# battery_pack.net
KiCad netlist of a schematic drawn in EAGLE
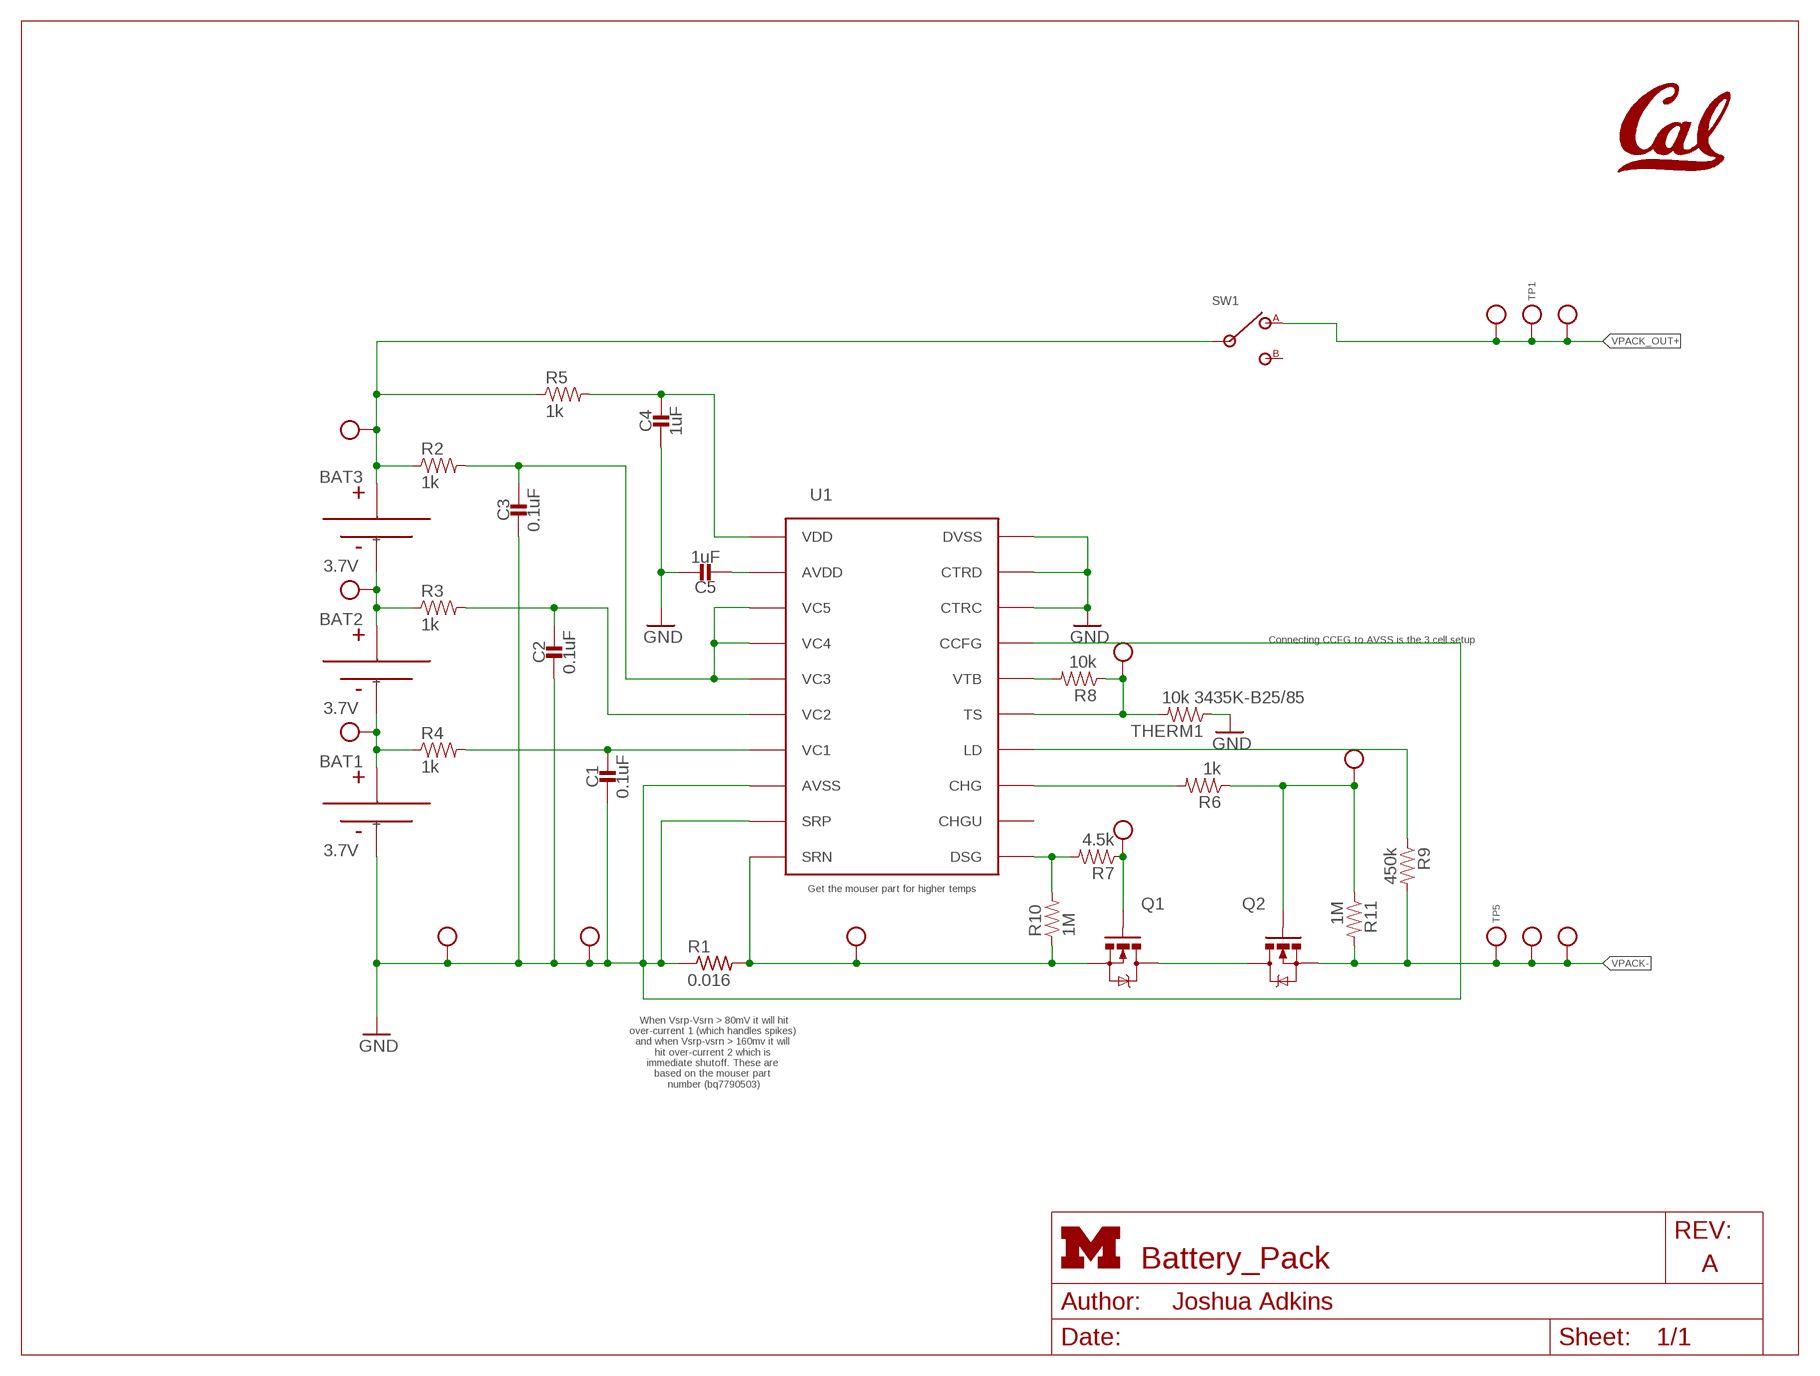
[diagram p0: schematic, sheet 1]

(export (version "E")
  (design (tool "Eeschema 10.0.6"))
  (components
    (comp (ref "BAT1")
      (value "3.7V")
      (footprint "eagle-import:PL-809797-1C")
      (libsource (lib "eagle-import") (part "BAT-CELL"))
    )
    (comp (ref "BAT2")
      (value "3.7V")
      (footprint "eagle-import:PL-809797-1C")
      (libsource (lib "eagle-import") (part "BAT-CELL"))
    )
    (comp (ref "BAT3")
      (value "3.7V")
      (footprint "eagle-import:PL-809797-1C")
      (libsource (lib "eagle-import") (part "BAT-CELL"))
    )
    (comp (ref "C1")
      (value "0.1uF")
      (footprint "eagle-import:0603_CAP")
      (description "CAP CER 0.1UF 25V Y5V 0603")
      (fields (field (name "MANUFACTURER") "Yageo") (field (name "MPN") "CC0603ZRY5V8BB104"))
      (libsource (lib "eagle-import") (part "CAPACITOR0603_CAP"))
    )
    (comp (ref "C2")
      (value "0.1uF")
      (footprint "eagle-import:0603_CAP")
      (description "CAP CER 0.1UF 25V Y5V 0603")
      (fields (field (name "MANUFACTURER") "Yageo") (field (name "MPN") "CC0603ZRY5V8BB104"))
      (libsource (lib "eagle-import") (part "CAPACITOR0603_CAP"))
    )
    (comp (ref "C3")
      (value "0.1uF")
      (footprint "eagle-import:0603_CAP")
      (description "CAP CER 0.1UF 25V Y5V 0603")
      (fields (field (name "MANUFACTURER") "Yageo") (field (name "MPN") "CC0603ZRY5V8BB104"))
      (libsource (lib "eagle-import") (part "CAPACITOR0603_CAP"))
    )
    (comp (ref "C4")
      (value "1uF")
      (footprint "eagle-import:0603_CAP")
      (description "CAP CER 1UF 25V X5R 0603")
      (fields (field (name "MANUFACTURER") "Yageo") (field (name "MPN") "CC0603KRX5R8BB105"))
      (libsource (lib "eagle-import") (part "CAPACITOR0603_CAP"))
    )
    (comp (ref "C5")
      (value "1uF")
      (footprint "eagle-import:0603_CAP")
      (description "CAP CER 1UF 25V X5R 0603")
      (fields (field (name "MANUFACTURER") "Yageo") (field (name "MPN") "CC0603KRX5R8BB105"))
      (libsource (lib "eagle-import") (part "CAPACITOR0603_CAP"))
    )
    (comp (ref "Q1")
      (value "MOSFET-NCHANNELFDD8580")
      (footprint "eagle-import:DPAK")
      (description "MOSFET N-CH 40V 50A DPAK")
      (fields (field (name "MANUFACTURER") "Fairchild Semiconductor") (field (name "MPN") "FDD8447L_F085"))
      (libsource (lib "eagle-import") (part "MOSFET-NCHANNELFDD8580"))
    )
    (comp (ref "Q2")
      (value "MOSFET-NCHANNELFDD8580")
      (footprint "eagle-import:DPAK")
      (description "MOSFET N-CH 40V 50A DPAK")
      (fields (field (name "MANUFACTURER") "Fairchild Semiconductor") (field (name "MPN") "FDD8447L_F085"))
      (libsource (lib "eagle-import") (part "MOSFET-NCHANNELFDD8580"))
    )
    (comp (ref "R1")
      (value "0.016")
      (footprint "eagle-import:R1206")
      (description "RES SMD 16 MOHM 1% 1W 1206")
      (fields (field (name "MANUFACTURER") "Panasonic") (field (name "MPN") "ERJ8CWFR016V"))
      (libsource (lib "eagle-import") (part "R-US_R1206"))
    )
    (comp (ref "R2")
      (value "1k")
      (footprint "eagle-import:0603-RES")
      (description "RES SMD 1K OHM 5% 1/10W 0603")
      (fields (field (name "MANUFACTURER") "Yageo") (field (name "MPN") "RC0603JR-071KL"))
      (libsource (lib "eagle-import") (part "RESISTOR0603_RES"))
    )
    (comp (ref "R3")
      (value "1k")
      (footprint "eagle-import:0603-RES")
      (description "RES SMD 1K OHM 5% 1/10W 0603")
      (fields (field (name "MANUFACTURER") "Yageo") (field (name "MPN") "RC0603JR-071KL"))
      (libsource (lib "eagle-import") (part "RESISTOR0603_RES"))
    )
    (comp (ref "R4")
      (value "1k")
      (footprint "eagle-import:0603-RES")
      (description "RES SMD 1K OHM 5% 1/10W 0603")
      (fields (field (name "MANUFACTURER") "Yageo") (field (name "MPN") "RC0603JR-071KL"))
      (libsource (lib "eagle-import") (part "RESISTOR0603_RES"))
    )
    (comp (ref "R5")
      (value "1k")
      (footprint "eagle-import:0603-RES")
      (description "RES SMD 1K OHM 5% 1/10W 0603")
      (fields (field (name "MANUFACTURER") "Yageo") (field (name "MPN") "RC0603JR-071KL"))
      (libsource (lib "eagle-import") (part "RESISTOR0603_RES"))
    )
    (comp (ref "R6")
      (value "1k")
      (footprint "eagle-import:0603-RES")
      (description "RES SMD 1K OHM 5% 1/10W 0603")
      (fields (field (name "MANUFACTURER") "Yageo") (field (name "MPN") "RC0603JR-071KL"))
      (libsource (lib "eagle-import") (part "RESISTOR0603_RES"))
    )
    (comp (ref "R7")
      (value "4.5k")
      (footprint "eagle-import:0603-RES")
      (description "RES SMD 4.53K OHM 1% 1/10W 0603")
      (fields (field (name "MANUFACTURER") "Yageo") (field (name "MPN") "RC0603FR-074K53L"))
      (libsource (lib "eagle-import") (part "RESISTOR0603_RES"))
    )
    (comp (ref "R8")
      (value "10k")
      (footprint "eagle-import:0603-RES")
      (description "RES SMD 10K OHM 5% 1/10W 0603")
      (fields (field (name "MANUFACTURER") "Yageo") (field (name "MPN") "RC0603JR-0710KL"))
      (libsource (lib "eagle-import") (part "RESISTOR0603_RES"))
    )
    (comp (ref "R9")
      (value "450k")
      (footprint "eagle-import:0603-RES")
      (description "RES SMD 453K OHM 1% 1/10W 0603")
      (fields (field (name "MANUFACTURER") "Yageo") (field (name "MPN") "RC0603FR-07453KL"))
      (libsource (lib "eagle-import") (part "RESISTOR0603_RES"))
    )
    (comp (ref "R10")
      (value "1M")
      (footprint "eagle-import:0603-RES")
      (description "RES SMD 1M OHM 5% 1/10W 0603")
      (fields (field (name "MANUFACTURER") "Yageo") (field (name "MPN") "RC0603JR-071ML"))
      (libsource (lib "eagle-import") (part "RESISTOR0603_RES"))
    )
    (comp (ref "R11")
      (value "1M")
      (footprint "eagle-import:0603-RES")
      (description "RES SMD 1M OHM 5% 1/10W 0603")
      (fields (field (name "MANUFACTURER") "Yageo") (field (name "MPN") "RC0603JR-071ML"))
      (libsource (lib "eagle-import") (part "RESISTOR0603_RES"))
    )
    (comp (ref "SW1")
      (value "500ASSP")
      (footprint "eagle-import:500ASSP")
      (fields (field (name "MANUFACTURER") "EWSITCH") (field (name "MPN") "500ASSP1M6QE"))
      (libsource (lib "eagle-import") (part "500ASSP"))
    )
    (comp (ref "THERM1")
      (value "10k 3435K-B25/85")
      (footprint "eagle-import:0603-RES")
      (description "NTC THERMISTOR 10K OHM 1% 0603")
      (fields (field (name "MANUFACTURER") "TDK") (field (name "MPN") "NTCG163JF103FT1"))
      (libsource (lib "eagle-import") (part "RESISTOR0603_RES"))
    )
    (comp (ref "TP1")
      (value "TEST_POINT_0.060IN")
      (footprint "eagle-import:TESTPOINT_0.060IN")
      (libsource (lib "eagle-import") (part "TEST_POINT_0.060IN"))
    )
    (comp (ref "TP2")
      (value "TEST_POINT_0.112IN")
      (footprint "eagle-import:TESTPOINT_0.112IN")
      (libsource (lib "eagle-import") (part "TEST_POINT_0.112IN"))
    )
    (comp (ref "TP3")
      (value "TEST_POINT_0.040IN")
      (footprint "eagle-import:TESTPOINT_0.040IN")
      (libsource (lib "eagle-import") (part "TEST_POINT_0.040IN"))
    )
    (comp (ref "TP4")
      (value "TEST_POINT_0.040IN")
      (footprint "eagle-import:TESTPOINT_0.040IN")
      (libsource (lib "eagle-import") (part "TEST_POINT_0.040IN"))
    )
    (comp (ref "TP5")
      (value "TEST_POINT_0.060IN")
      (footprint "eagle-import:TESTPOINT_0.060IN")
      (libsource (lib "eagle-import") (part "TEST_POINT_0.060IN"))
    )
    (comp (ref "TP6")
      (value "TEST_POINT_0.112IN")
      (footprint "eagle-import:TESTPOINT_0.112IN")
      (libsource (lib "eagle-import") (part "TEST_POINT_0.112IN"))
    )
    (comp (ref "TP7")
      (value "TEST_POINT_0.112IN")
      (footprint "eagle-import:TESTPOINT_0.112IN")
      (libsource (lib "eagle-import") (part "TEST_POINT_0.112IN"))
    )
    (comp (ref "TP8")
      (value "TEST_POINT_0.112IN")
      (footprint "eagle-import:TESTPOINT_0.112IN")
      (libsource (lib "eagle-import") (part "TEST_POINT_0.112IN"))
    )
    (comp (ref "TP9")
      (value "TEST_POINT_0.040IN")
      (footprint "eagle-import:TESTPOINT_0.040IN")
      (libsource (lib "eagle-import") (part "TEST_POINT_0.040IN"))
    )
    (comp (ref "TP10")
      (value "TEST_POINT_0.040IN")
      (footprint "eagle-import:TESTPOINT_0.040IN")
      (libsource (lib "eagle-import") (part "TEST_POINT_0.040IN"))
    )
    (comp (ref "TP11")
      (value "TEST_POINT_0.040IN")
      (footprint "eagle-import:TESTPOINT_0.040IN")
      (libsource (lib "eagle-import") (part "TEST_POINT_0.040IN"))
    )
    (comp (ref "TP12")
      (value "TEST_POINT_0.040IN")
      (footprint "eagle-import:TESTPOINT_0.040IN")
      (libsource (lib "eagle-import") (part "TEST_POINT_0.040IN"))
    )
    (comp (ref "TP13")
      (value "TEST_POINT_0.040IN")
      (footprint "eagle-import:TESTPOINT_0.040IN")
      (libsource (lib "eagle-import") (part "TEST_POINT_0.040IN"))
    )
    (comp (ref "TP14")
      (value "TEST_POINT_0.112IN")
      (footprint "eagle-import:TESTPOINT_0.112IN")
      (libsource (lib "eagle-import") (part "TEST_POINT_0.112IN"))
    )
    (comp (ref "TP15")
      (value "TEST_POINT_0.112IN")
      (footprint "eagle-import:TESTPOINT_0.112IN")
      (libsource (lib "eagle-import") (part "TEST_POINT_0.112IN"))
    )
    (comp (ref "U$1")
      (value "UCB_CAL500MIL")
      (footprint "eagle-import:UCB_CAL_500MIL")
      (libsource (lib "eagle-import") (part "UCB_CAL500MIL"))
    )
    (comp (ref "U1")
      (value "BQ77904")
      (footprint "eagle-import:TSSOP-20_6MM")
      (fields (field (name "MANUFACTURER") "TI") (field (name "MPN") "BQ7790503PW"))
      (libsource (lib "eagle-import") (part "BQ77904"))
    )
  )
  (nets
    (net (code "1") (name "GND") (class "Default")
      (node (ref "BAT1") (pin "-") (pinfunction "-_-") (pintype "bidirectional"))
      (node (ref "C1") (pin "2") (pinfunction "2_2") (pintype "bidirectional"))
      (node (ref "C2") (pin "2") (pinfunction "2_2") (pintype "bidirectional"))
      (node (ref "C3") (pin "2") (pinfunction "2_2") (pintype "bidirectional"))
      (node (ref "C4") (pin "2") (pinfunction "2_2") (pintype "bidirectional"))
      (node (ref "C5") (pin "1") (pinfunction "1_1") (pintype "bidirectional"))
      (node (ref "R1") (pin "1") (pinfunction "1_1") (pintype "passive"))
      (node (ref "THERM1") (pin "1") (pinfunction "1_1") (pintype "passive"))
      (node (ref "TP7") (pin "1") (pinfunction "TESTPOINT_1") (pintype "bidirectional"))
      (node (ref "TP9") (pin "TESTPOINT") (pinfunction "TESTPOINT_TESTPOINT") (pintype "bidirectional"))
      (node (ref "U1") (pin "17") (pinfunction "CCFG_17") (pintype "bidirectional"))
      (node (ref "U1") (pin "18") (pinfunction "CTRC_18") (pintype "bidirectional"))
      (node (ref "U1") (pin "19") (pinfunction "CTRD_19") (pintype "bidirectional"))
      (node (ref "U1") (pin "20") (pinfunction "DVSS_20") (pintype "bidirectional"))
      (node (ref "U1") (pin "8") (pinfunction "AVSS_8") (pintype "bidirectional"))
      (node (ref "U1") (pin "9") (pinfunction "SRP_9") (pintype "bidirectional"))
    )
    (net (code "2") (name "Net-(Q1-D)") (class "Default")
      (node (ref "Q1") (pin "4") (pinfunction "D_4") (pintype "passive"))
      (node (ref "Q2") (pin "4") (pinfunction "D_4") (pintype "passive"))
    )
    (net (code "3") (name "Net-(Q1-G)") (class "Default")
      (node (ref "Q1") (pin "1") (pinfunction "G_1") (pintype "passive"))
      (node (ref "R7") (pin "1") (pinfunction "1_1") (pintype "passive"))
      (node (ref "TP11") (pin "TESTPOINT") (pinfunction "TESTPOINT_TESTPOINT") (pintype "bidirectional"))
    )
    (net (code "4") (name "Net-(Q1-S)") (class "Default")
      (node (ref "Q1") (pin "3") (pinfunction "S_3") (pintype "passive"))
      (node (ref "R1") (pin "2") (pinfunction "2_2") (pintype "passive"))
      (node (ref "R10") (pin "1") (pinfunction "1_1") (pintype "passive"))
      (node (ref "TP10") (pin "TESTPOINT") (pinfunction "TESTPOINT_TESTPOINT") (pintype "bidirectional"))
      (node (ref "U1") (pin "10") (pinfunction "SRN_10") (pintype "bidirectional"))
    )
    (net (code "5") (name "Net-(Q2-G)") (class "Default")
      (node (ref "Q2") (pin "1") (pinfunction "G_1") (pintype "passive"))
      (node (ref "R11") (pin "1") (pinfunction "1_1") (pintype "passive"))
      (node (ref "R6") (pin "1") (pinfunction "1_1") (pintype "passive"))
      (node (ref "TP12") (pin "TESTPOINT") (pinfunction "TESTPOINT_TESTPOINT") (pintype "bidirectional"))
    )
    (net (code "6") (name "Net-(TP8-TESTPOINT)") (class "Default")
      (node (ref "BAT3") (pin "+") (pinfunction "+_+") (pintype "bidirectional"))
      (node (ref "R2") (pin "1") (pinfunction "1_1") (pintype "passive"))
      (node (ref "R5") (pin "1") (pinfunction "1_1") (pintype "passive"))
      (node (ref "SW1") (pin "2") (pinfunction "2_2") (pintype "bidirectional"))
      (node (ref "TP8") (pin "1") (pinfunction "TESTPOINT_1") (pintype "bidirectional"))
    )
    (net (code "7") (name "Net-(TP14-TESTPOINT)") (class "Default")
      (node (ref "BAT2") (pin "+") (pinfunction "+_+") (pintype "bidirectional"))
      (node (ref "BAT3") (pin "-") (pinfunction "-_-") (pintype "bidirectional"))
      (node (ref "R3") (pin "1") (pinfunction "1_1") (pintype "passive"))
      (node (ref "TP14") (pin "1") (pinfunction "TESTPOINT_1") (pintype "bidirectional"))
    )
    (net (code "8") (name "Net-(TP15-TESTPOINT)") (class "Default")
      (node (ref "BAT1") (pin "+") (pinfunction "+_+") (pintype "bidirectional"))
      (node (ref "BAT2") (pin "-") (pinfunction "-_-") (pintype "bidirectional"))
      (node (ref "R4") (pin "1") (pinfunction "1_1") (pintype "passive"))
      (node (ref "TP15") (pin "1") (pinfunction "TESTPOINT_1") (pintype "bidirectional"))
    )
    (net (code "9") (name "Net-(U1-AVDD)") (class "Default")
      (node (ref "C5") (pin "2") (pinfunction "2_2") (pintype "bidirectional"))
      (node (ref "U1") (pin "2") (pinfunction "AVDD_2") (pintype "bidirectional"))
    )
    (net (code "10") (name "Net-(U1-CHG)") (class "Default")
      (node (ref "R6") (pin "2") (pinfunction "2_2") (pintype "passive"))
      (node (ref "U1") (pin "13") (pinfunction "CHG_13") (pintype "bidirectional"))
    )
    (net (code "11") (name "Net-(U1-DSG)") (class "Default")
      (node (ref "R10") (pin "2") (pinfunction "2_2") (pintype "passive"))
      (node (ref "R7") (pin "2") (pinfunction "2_2") (pintype "passive"))
      (node (ref "U1") (pin "11") (pinfunction "DSG_11") (pintype "bidirectional"))
    )
    (net (code "12") (name "Net-(U1-LD)") (class "Default")
      (node (ref "R9") (pin "1") (pinfunction "1_1") (pintype "passive"))
      (node (ref "U1") (pin "14") (pinfunction "LD_14") (pintype "bidirectional"))
    )
    (net (code "13") (name "Net-(U1-TS)") (class "Default")
      (node (ref "R8") (pin "1") (pinfunction "1_1") (pintype "passive"))
      (node (ref "THERM1") (pin "2") (pinfunction "2_2") (pintype "passive"))
      (node (ref "TP13") (pin "TESTPOINT") (pinfunction "TESTPOINT_TESTPOINT") (pintype "bidirectional"))
      (node (ref "U1") (pin "15") (pinfunction "TS_15") (pintype "bidirectional"))
    )
    (net (code "14") (name "Net-(U1-VC1)") (class "Default")
      (node (ref "C1") (pin "1") (pinfunction "1_1") (pintype "bidirectional"))
      (node (ref "R4") (pin "2") (pinfunction "2_2") (pintype "passive"))
      (node (ref "U1") (pin "7") (pinfunction "VC1_7") (pintype "bidirectional"))
    )
    (net (code "15") (name "Net-(U1-VC2)") (class "Default")
      (node (ref "C2") (pin "1") (pinfunction "1_1") (pintype "bidirectional"))
      (node (ref "R3") (pin "2") (pinfunction "2_2") (pintype "passive"))
      (node (ref "U1") (pin "6") (pinfunction "VC2_6") (pintype "bidirectional"))
    )
    (net (code "16") (name "Net-(U1-VC3)") (class "Default")
      (node (ref "C3") (pin "1") (pinfunction "1_1") (pintype "bidirectional"))
      (node (ref "R2") (pin "2") (pinfunction "2_2") (pintype "passive"))
      (node (ref "U1") (pin "3") (pinfunction "VC5_3") (pintype "bidirectional"))
      (node (ref "U1") (pin "4") (pinfunction "VC4_4") (pintype "bidirectional"))
      (node (ref "U1") (pin "5") (pinfunction "VC3_5") (pintype "bidirectional"))
    )
    (net (code "17") (name "Net-(U1-VDD)") (class "Default")
      (node (ref "C4") (pin "1") (pinfunction "1_1") (pintype "bidirectional"))
      (node (ref "R5") (pin "2") (pinfunction "2_2") (pintype "passive"))
      (node (ref "U1") (pin "1") (pinfunction "VDD_1") (pintype "bidirectional"))
    )
    (net (code "18") (name "Net-(U1-VTB)") (class "Default")
      (node (ref "R8") (pin "2") (pinfunction "2_2") (pintype "passive"))
      (node (ref "U1") (pin "16") (pinfunction "VTB_16") (pintype "bidirectional"))
    )
    (net (code "19") (name "VPACK-") (class "Default")
      (node (ref "Q2") (pin "3") (pinfunction "S_3") (pintype "passive"))
      (node (ref "R11") (pin "2") (pinfunction "2_2") (pintype "passive"))
      (node (ref "R9") (pin "2") (pinfunction "2_2") (pintype "passive"))
      (node (ref "TP2") (pin "1") (pinfunction "TESTPOINT_1") (pintype "bidirectional"))
      (node (ref "TP4") (pin "TESTPOINT") (pinfunction "TESTPOINT_TESTPOINT") (pintype "bidirectional"))
      (node (ref "TP5") (pin "TESTPOINT") (pinfunction "TESTPOINT_TESTPOINT") (pintype "bidirectional"))
    )
    (net (code "20") (name "VPACK_OUT+") (class "Default")
      (node (ref "SW1") (pin "1") (pinfunction "1_1") (pintype "bidirectional"))
      (node (ref "TP1") (pin "TESTPOINT") (pinfunction "TESTPOINT_TESTPOINT") (pintype "bidirectional"))
      (node (ref "TP3") (pin "TESTPOINT") (pinfunction "TESTPOINT_TESTPOINT") (pintype "bidirectional"))
      (node (ref "TP6") (pin "1") (pinfunction "TESTPOINT_1") (pintype "bidirectional"))
    )
    (net (code "21") (name "unconnected-(SW1-Pad3)") (class "Default")
      (node (ref "SW1") (pin "3") (pinfunction "3_3") (pintype "bidirectional"))
    )
    (net (code "22") (name "unconnected-(U1-CHGU-Pad12)") (class "Default")
      (node (ref "U1") (pin "12") (pinfunction "CHGU_12") (pintype "bidirectional"))
    )
  )
)
